# ATtiny25_2020-08-31_22-25-55.net
KiCad netlist of a schematic drawn in EasyEDA
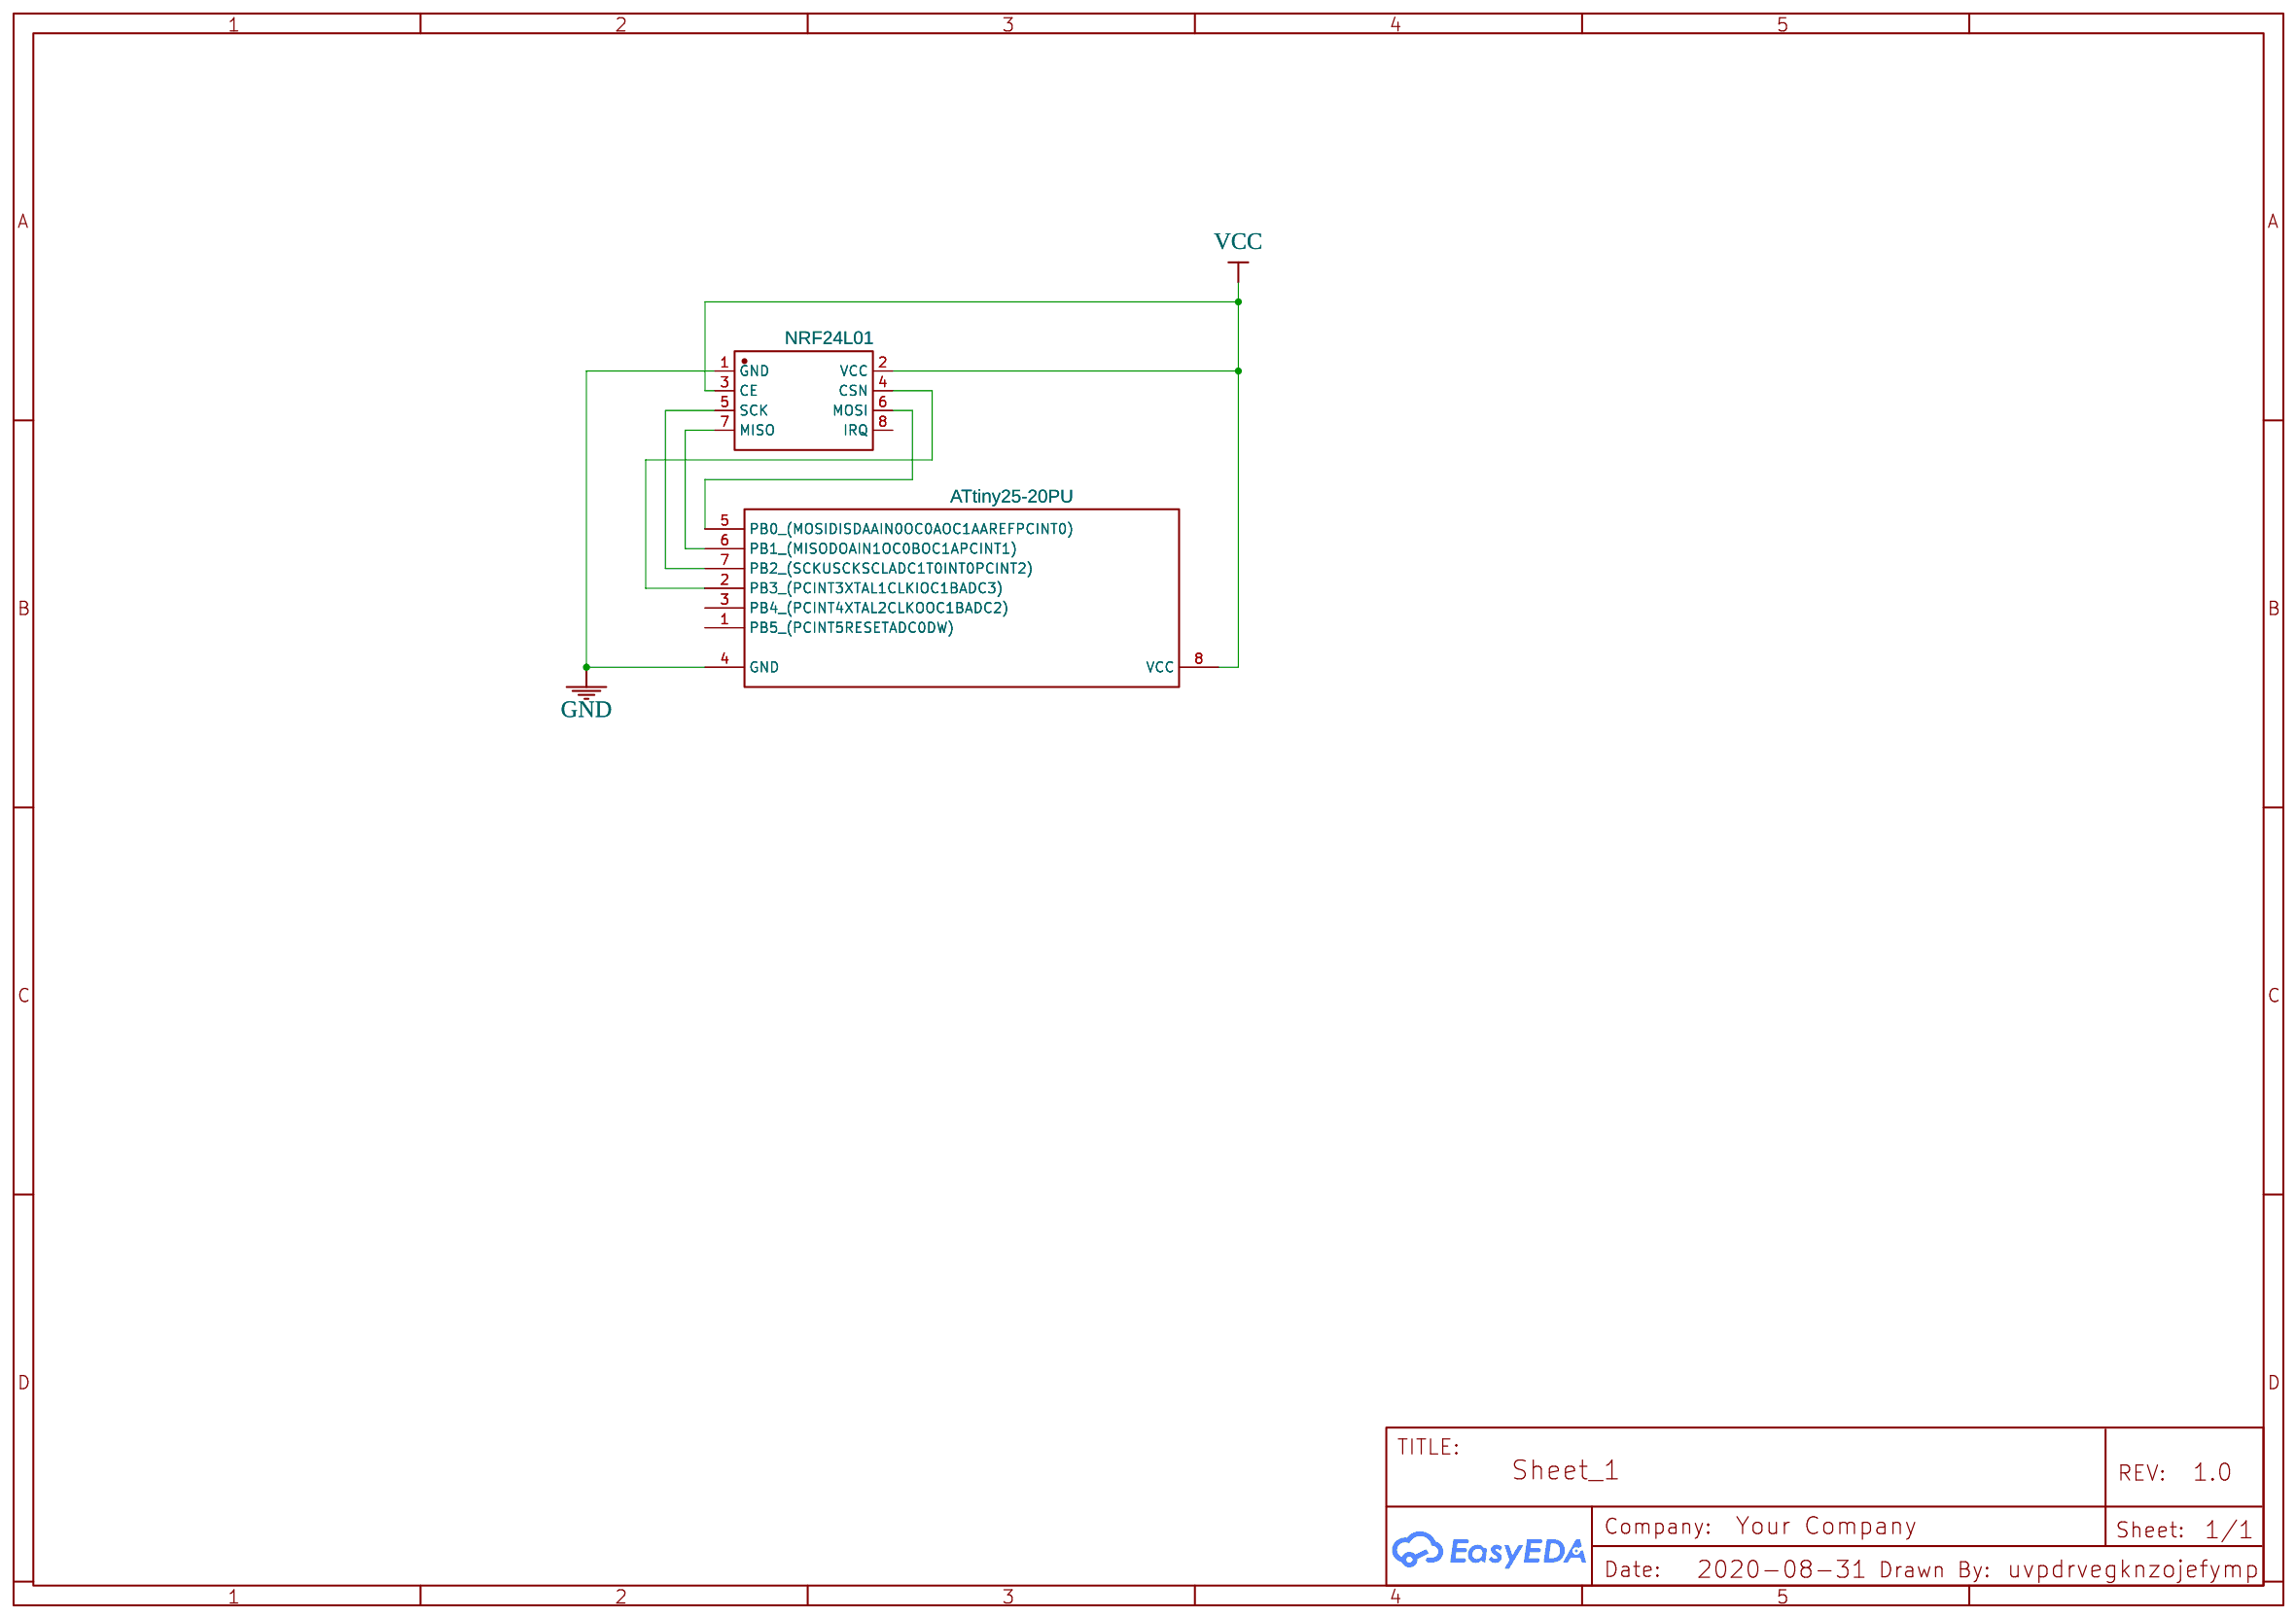
[diagram p0: schematic sheet]

(export (version "E")
  (design (tool "Eeschema 10.0.6"))
  (components
    (comp (ref "MK1")
      (value "NRF24L01")
      (fields
        (field (name "BOM_Manufacturer Part") "NRF24L01+功率加强版绑定2.4Gwireless module")
        (field (name "BOM_Supplier Part") "C90751")
      )
      (libsource (lib "") (part "NRF24L01"))
    )
    (comp (ref "U1") (value "ATtiny25-20PU") (libsource (lib "") (part "ATtiny25-20PU")))
  )
  (nets
    (net (code "1") (name "GND") (class "Default")
      (node (ref "MK1") (pin "1") (pinfunction "GND_1") (pintype "unspecified"))
      (node (ref "U1") (pin "4") (pinfunction "GND_4") (pintype "passive"))
    )
    (net (code "2") (name "Net-(MK1-CSN)") (class "Default")
      (node (ref "MK1") (pin "4") (pinfunction "CSN_4") (pintype "unspecified"))
      (node (ref "U1") (pin "2") (pinfunction "PB3_(PCINT3XTAL1CLKIOC1BADC3)_2") (pintype "bidirectional"))
    )
    (net (code "3") (name "Net-(MK1-MISO)") (class "Default")
      (node (ref "MK1") (pin "7") (pinfunction "MISO_7") (pintype "unspecified"))
      (node (ref "U1") (pin "6") (pinfunction "PB1_(MISODOAIN1OC0BOC1APCINT1)_6") (pintype "bidirectional"))
    )
    (net (code "4") (name "Net-(MK1-MOSI)") (class "Default")
      (node (ref "MK1") (pin "6") (pinfunction "MOSI_6") (pintype "unspecified"))
      (node (ref "U1") (pin "5") (pinfunction "PB0_(MOSIDISDAAIN0OC0AOC1AAREFPCINT0)_5") (pintype "bidirectional"))
    )
    (net (code "5") (name "Net-(MK1-SCK)") (class "Default")
      (node (ref "MK1") (pin "5") (pinfunction "SCK_5") (pintype "unspecified"))
      (node (ref "U1") (pin "7") (pinfunction "PB2_(SCKUSCKSCLADC1T0INT0PCINT2)_7") (pintype "bidirectional"))
    )
    (net (code "6") (name "VCC") (class "Default")
      (node (ref "MK1") (pin "2") (pinfunction "VCC_2") (pintype "unspecified"))
      (node (ref "MK1") (pin "3") (pinfunction "CE_3") (pintype "unspecified"))
      (node (ref "U1") (pin "8") (pinfunction "VCC_8") (pintype "passive"))
    )
    (net (code "7") (name "unconnected-(MK1-IRQ-Pad8)") (class "Default")
      (node (ref "MK1") (pin "8") (pinfunction "IRQ_8") (pintype "unspecified"))
    )
    (net (code "8") (name "unconnected-(U1-PB4_(PCINT4XTAL2CLKOOC1BADC2)-Pad3)") (class "Default")
      (node (ref "U1") (pin "3") (pinfunction "PB4_(PCINT4XTAL2CLKOOC1BADC2)_3") (pintype "bidirectional"))
    )
    (net (code "9") (name "unconnected-(U1-PB5_(PCINT5RESETADC0DW)-Pad1)") (class "Default")
      (node (ref "U1") (pin "1") (pinfunction "PB5_(PCINT5RESETADC0DW)_1") (pintype "bidirectional"))
    )
  )
)
